# Airq_easyeda.net
KiCad netlist of a schematic drawn in EasyEDA
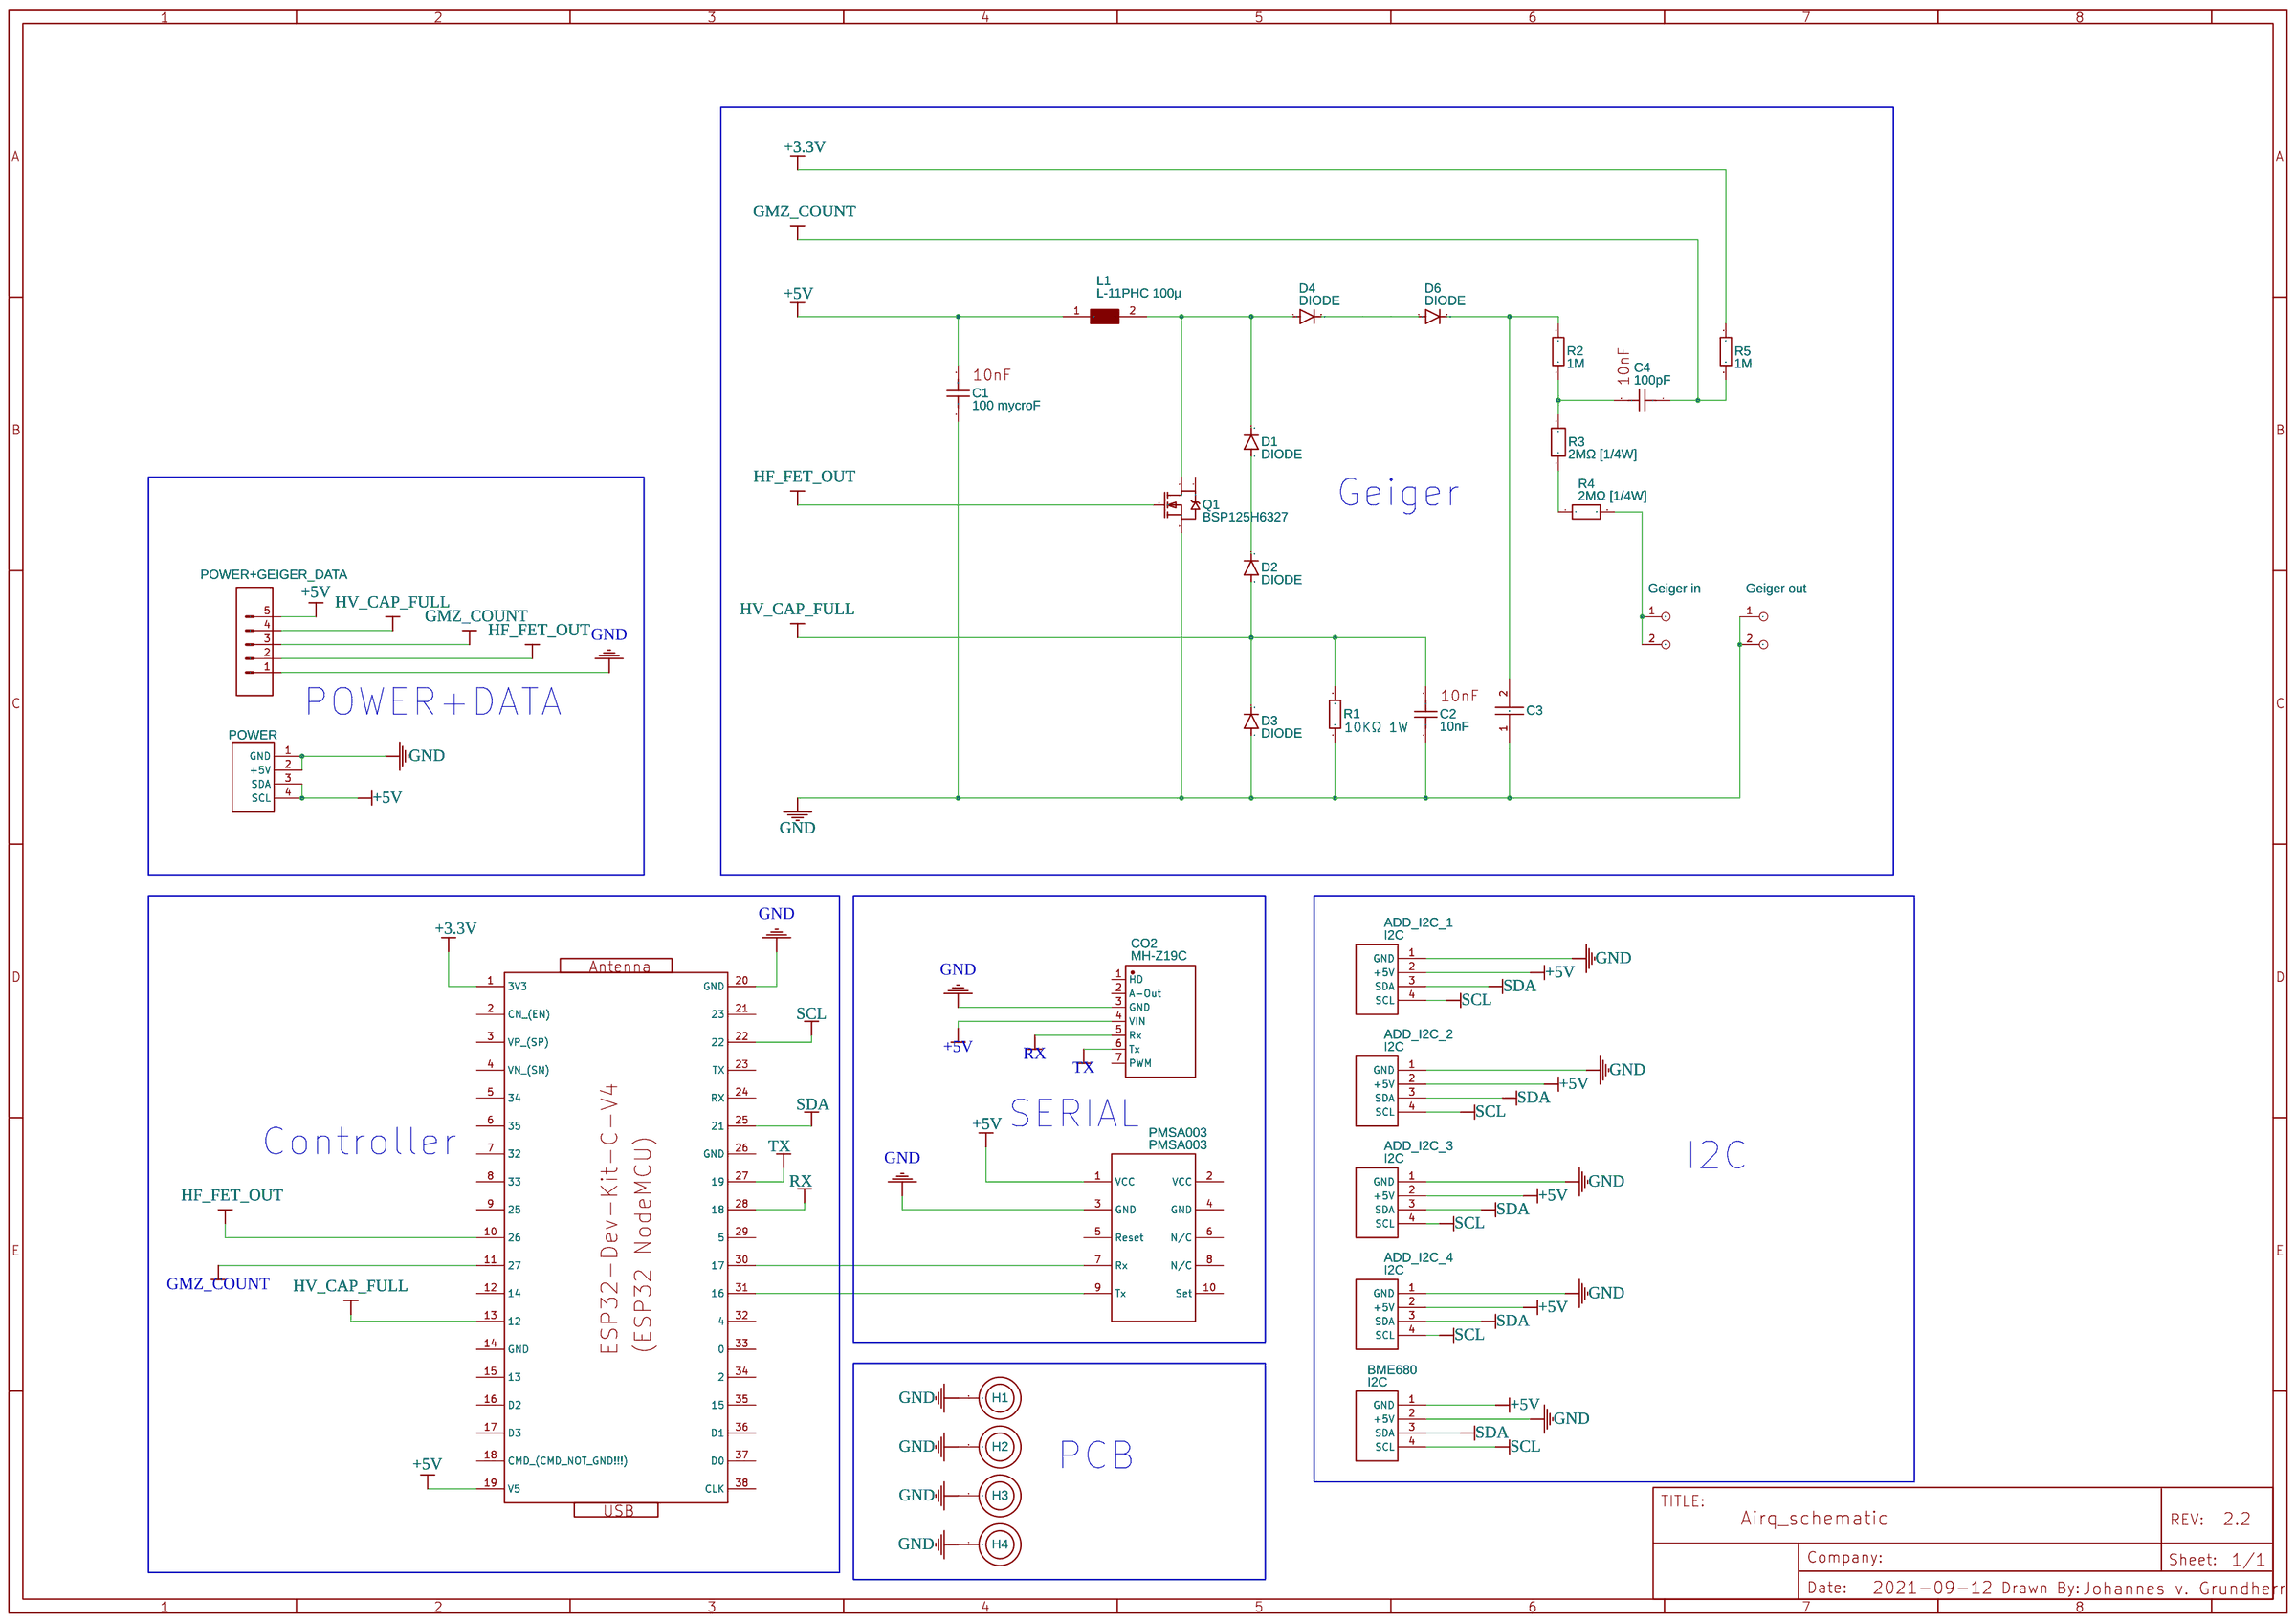
[diagram p0: schematic sheet]

(export (version "E")
  (design (tool "Eeschema 10.0.6"))
  (components
    (comp (ref "ADD_I2C_1") (value "I2C") (libsource (lib "") (part "I2C")))
    (comp (ref "ADD_I2C_2") (value "I2C") (libsource (lib "") (part "I2C")))
    (comp (ref "ADD_I2C_3") (value "I2C") (libsource (lib "") (part "I2C")))
    (comp (ref "ADD_I2C_4") (value "I2C") (libsource (lib "") (part "I2C")))
    (comp (ref "BME680") (value "I2C") (libsource (lib "") (part "I2C_1")))
    (comp (ref "C1") (value "100 mycroF") (libsource (lib "") (part "10nF")))
    (comp (ref "C2") (value "10nF") (libsource (lib "") (part "10nF")))
    (comp (ref "C3") (value "Wima, MKP4, 100nF, 630V") (libsource (lib "") (part "Wima, MKP4, 100nF, 630V")))
    (comp (ref "C4") (value "100pF") (libsource (lib "") (part "10nF_1")))
    (comp (ref "CO2")
      (value "MH-Z19C")
      (fields
        (field (name "BOM_Supplier Part") "https://github.com/WifWaf/MH-Z19/tree/master/examples/BasicUsage")
      )
      (libsource (lib "") (part "MH-Z19C"))
    )
    (comp (ref "D1") (value "DIODE") (libsource (lib "") (part "DIODE")))
    (comp (ref "D2") (value "DIODE") (libsource (lib "") (part "DIODE")))
    (comp (ref "D3") (value "DIODE") (libsource (lib "") (part "DIODE")))
    (comp (ref "D4") (value "DIODE") (libsource (lib "") (part "DIODE_1")))
    (comp (ref "D6") (value "DIODE") (libsource (lib "") (part "DIODE_1")))
    (comp (ref "H1") (value "HoleHole") (libsource (lib "") (part "HoleHole")))
    (comp (ref "H2") (value "HoleHole") (libsource (lib "") (part "HoleHole")))
    (comp (ref "H3") (value "HoleHole") (libsource (lib "") (part "HoleHole")))
    (comp (ref "H4") (value "HoleHole") (libsource (lib "") (part "HoleHole")))
    (comp (ref "JP1") (value "Geiger in") (libsource (lib "") (part "2 Pin Header")))
    (comp (ref "JP2") (value "Geiger out") (libsource (lib "") (part "2 Pin Header")))
    (comp (ref "L1") (value "L-11PHC 100µ") (libsource (lib "") (part "L-11PHC 100µ")))
    (comp (ref "PMSA003") (value "PMSA003") (libsource (lib "") (part "PMSA003")))
    (comp (ref "POWER") (value "Power") (libsource (lib "") (part "I2C_2")))
    (comp (ref "POWER+GEIGER_DATA") (value "POWER+GEIGER_DATA") (libsource (lib "") (part "Header 5pin")))
    (comp (ref "Q1")
      (value "BSP125H6327")
      (fields (field (name "BOM_Supplier Part") "C123756"))
      (libsource (lib "") (part "BSP125H6327"))
    )
    (comp (ref "R1")
      (value "10KΩ 1W")
      (fields
        (field (name "BOM_Manufacturer Part") "MFR0W4F1004A50")
        (field (name "BOM_Supplier Part") "C58596")
      )
      (libsource (lib "") (part "1M OHM_1"))
    )
    (comp (ref "R2")
      (value "1M")
      (fields
        (field (name "BOM_Manufacturer Part") "MFR0W4F1004A50")
        (field (name "BOM_Supplier Part") "C58596")
      )
      (libsource (lib "") (part "1M OHM_1"))
    )
    (comp (ref "R3")
      (value "2MΩ [1/4W]")
      (fields (field (name "BOM_Supplier Part") "C720290"))
      (libsource (lib "") (part "4.7MΩ [1/4W]"))
    )
    (comp (ref "R4")
      (value "2MΩ [1/4W]")
      (fields (field (name "BOM_Supplier Part") "C720290"))
      (libsource (lib "") (part "4.7MΩ [1/4W]_1"))
    )
    (comp (ref "R5")
      (value "1M")
      (fields
        (field (name "BOM_Manufacturer Part") "MFR0W4F1004A50")
        (field (name "BOM_Supplier Part") "C58596")
      )
      (libsource (lib "") (part "1M OHM"))
    )
    (comp (ref "U1")
      (value "AZDelivery_ESP32_NodeMCU")
      (libsource (lib "") (part "AZDelivery_ESP32_NodeMCU"))
    )
  )
  (nets
    (net (code "1") (name "+3.3V") (class "Default")
      (node (ref "R5") (pin "1") (pinfunction "1_1") (pintype "input"))
      (node (ref "U1") (pin "1") (pinfunction "3V3_1") (pintype "unspecified"))
    )
    (net (code "2") (name "+5V") (class "Default")
      (node (ref "ADD_I2C_1") (pin "2") (pinfunction "+5V_2") (pintype "unspecified"))
      (node (ref "ADD_I2C_2") (pin "2") (pinfunction "+5V_2") (pintype "unspecified"))
      (node (ref "ADD_I2C_3") (pin "2") (pinfunction "+5V_2") (pintype "unspecified"))
      (node (ref "ADD_I2C_4") (pin "2") (pinfunction "+5V_2") (pintype "unspecified"))
      (node (ref "BME680") (pin "1") (pinfunction "GND_1") (pintype "unspecified"))
      (node (ref "C1") (pin "2") (pinfunction "2_2") (pintype "unspecified"))
      (node (ref "CO2") (pin "4") (pinfunction "VIN_4") (pintype "passive"))
      (node (ref "L1") (pin "1") (pinfunction "1_1") (pintype "unspecified"))
      (node (ref "PMSA003") (pin "1") (pinfunction "VCC_1") (pintype "unspecified"))
      (node (ref "POWER") (pin "3") (pinfunction "SDA_3") (pintype "unspecified"))
      (node (ref "POWER") (pin "4") (pinfunction "SCL_4") (pintype "unspecified"))
      (node (ref "POWER+GEIGER_DATA") (pin "5") (pinfunction "1_5") (pintype "unspecified"))
      (node (ref "U1") (pin "19") (pinfunction "V5_19") (pintype "unspecified"))
    )
    (net (code "3") (name "GMZ_COUNT") (class "Default")
      (node (ref "C4") (pin "1") (pinfunction "1_1") (pintype "unspecified"))
      (node (ref "POWER+GEIGER_DATA") (pin "3") (pinfunction "1_3") (pintype "unspecified"))
      (node (ref "R5") (pin "2") (pinfunction "2_2") (pintype "input"))
      (node (ref "U1") (pin "11") (pinfunction "27_11") (pintype "unspecified"))
    )
    (net (code "4") (name "GND") (class "Default")
      (node (ref "ADD_I2C_1") (pin "1") (pinfunction "GND_1") (pintype "unspecified"))
      (node (ref "ADD_I2C_2") (pin "1") (pinfunction "GND_1") (pintype "unspecified"))
      (node (ref "ADD_I2C_3") (pin "1") (pinfunction "GND_1") (pintype "unspecified"))
      (node (ref "ADD_I2C_4") (pin "1") (pinfunction "GND_1") (pintype "unspecified"))
      (node (ref "BME680") (pin "2") (pinfunction "+5V_2") (pintype "unspecified"))
      (node (ref "C1") (pin "1") (pinfunction "1_1") (pintype "unspecified"))
      (node (ref "C2") (pin "1") (pinfunction "1_1") (pintype "unspecified"))
      (node (ref "C3") (pin "1") (pinfunction "1_1") (pintype "unspecified"))
      (node (ref "CO2") (pin "3") (pinfunction "GND_3") (pintype "passive"))
      (node (ref "D3") (pin "A") (pinfunction "A_A") (pintype "unspecified"))
      (node (ref "H1") (pin "1") (pinfunction "1_1") (pintype "bidirectional"))
      (node (ref "H2") (pin "1") (pinfunction "1_1") (pintype "bidirectional"))
      (node (ref "H3") (pin "1") (pinfunction "1_1") (pintype "bidirectional"))
      (node (ref "H4") (pin "1") (pinfunction "1_1") (pintype "bidirectional"))
      (node (ref "JP2") (pin "1") (pinfunction "1_1") (pintype "unspecified"))
      (node (ref "JP2") (pin "2") (pinfunction "2_2") (pintype "unspecified"))
      (node (ref "PMSA003") (pin "3") (pinfunction "GND_3") (pintype "unspecified"))
      (node (ref "POWER") (pin "1") (pinfunction "GND_1") (pintype "unspecified"))
      (node (ref "POWER") (pin "2") (pinfunction "+5V_2") (pintype "unspecified"))
      (node (ref "POWER+GEIGER_DATA") (pin "1") (pinfunction "1_1") (pintype "unspecified"))
      (node (ref "Q1") (pin "3") (pinfunction "S_3") (pintype "unspecified"))
      (node (ref "R1") (pin "1") (pinfunction "1_1") (pintype "input"))
      (node (ref "U1") (pin "20") (pinfunction "GND_20") (pintype "unspecified"))
    )
    (net (code "5") (name "HF_FET_OUT") (class "Default")
      (node (ref "POWER+GEIGER_DATA") (pin "2") (pinfunction "2_2") (pintype "unspecified"))
      (node (ref "Q1") (pin "1") (pinfunction "G_1") (pintype "unspecified"))
      (node (ref "U1") (pin "10") (pinfunction "26_10") (pintype "unspecified"))
    )
    (net (code "6") (name "HV_CAP_FULL") (class "Default")
      (node (ref "C2") (pin "2") (pinfunction "2_2") (pintype "unspecified"))
      (node (ref "D2") (pin "A") (pinfunction "A_A") (pintype "unspecified"))
      (node (ref "D3") (pin "C") (pinfunction "C_C") (pintype "unspecified"))
      (node (ref "POWER+GEIGER_DATA") (pin "4") (pinfunction "2_4") (pintype "unspecified"))
      (node (ref "R1") (pin "2") (pinfunction "2_2") (pintype "input"))
      (node (ref "U1") (pin "13") (pinfunction "12_13") (pintype "unspecified"))
    )
    (net (code "7") (name "Net-(C3-Pad2)") (class "Default")
      (node (ref "C3") (pin "2") (pinfunction "2_2") (pintype "unspecified"))
      (node (ref "D6") (pin "C") (pinfunction "C_C") (pintype "unspecified"))
      (node (ref "R2") (pin "2") (pinfunction "2_2") (pintype "input"))
    )
    (net (code "8") (name "Net-(C4-Pad2)") (class "Default")
      (node (ref "C4") (pin "2") (pinfunction "2_2") (pintype "unspecified"))
      (node (ref "R2") (pin "1") (pinfunction "1_1") (pintype "input"))
      (node (ref "R3") (pin "2") (pinfunction "2_2") (pintype "unspecified"))
    )
    (net (code "9") (name "Net-(D1-PadA)") (class "Default")
      (node (ref "D1") (pin "A") (pinfunction "A_A") (pintype "unspecified"))
      (node (ref "D2") (pin "C") (pinfunction "C_C") (pintype "unspecified"))
    )
    (net (code "10") (name "Net-(D1-PadC)") (class "Default")
      (node (ref "D1") (pin "C") (pinfunction "C_C") (pintype "unspecified"))
      (node (ref "D4") (pin "A") (pinfunction "A_A") (pintype "unspecified"))
      (node (ref "L1") (pin "2") (pinfunction "2_2") (pintype "unspecified"))
      (node (ref "Q1") (pin "2") (pinfunction "D_2") (pintype "unspecified"))
    )
    (net (code "11") (name "Net-(D4-PadC)") (class "Default")
      (node (ref "D4") (pin "C") (pinfunction "C_C") (pintype "unspecified"))
      (node (ref "D6") (pin "A") (pinfunction "A_A") (pintype "unspecified"))
    )
    (net (code "12") (name "Net-(JP1-Pad1)") (class "Default")
      (node (ref "JP1") (pin "1") (pinfunction "1_1") (pintype "unspecified"))
      (node (ref "JP1") (pin "2") (pinfunction "2_2") (pintype "unspecified"))
      (node (ref "R4") (pin "2") (pinfunction "2_2") (pintype "unspecified"))
    )
    (net (code "13") (name "Net-(PMSA003-Rx)") (class "Default")
      (node (ref "PMSA003") (pin "7") (pinfunction "Rx_7") (pintype "unspecified"))
      (node (ref "U1") (pin "30") (pinfunction "17_30") (pintype "unspecified"))
    )
    (net (code "14") (name "Net-(PMSA003-Tx)") (class "Default")
      (node (ref "PMSA003") (pin "9") (pinfunction "Tx_9") (pintype "unspecified"))
      (node (ref "U1") (pin "31") (pinfunction "16_31") (pintype "unspecified"))
    )
    (net (code "15") (name "Net-(R3-Pad1)") (class "Default")
      (node (ref "R3") (pin "1") (pinfunction "1_1") (pintype "unspecified"))
      (node (ref "R4") (pin "1") (pinfunction "1_1") (pintype "unspecified"))
    )
    (net (code "16") (name "RX") (class "Default")
      (node (ref "CO2") (pin "5") (pinfunction "Rx_5") (pintype "bidirectional"))
      (node (ref "U1") (pin "28") (pinfunction "18_28") (pintype "unspecified"))
    )
    (net (code "17") (name "SCL") (class "Default")
      (node (ref "ADD_I2C_1") (pin "4") (pinfunction "SCL_4") (pintype "unspecified"))
      (node (ref "ADD_I2C_2") (pin "4") (pinfunction "SCL_4") (pintype "unspecified"))
      (node (ref "ADD_I2C_3") (pin "4") (pinfunction "SCL_4") (pintype "unspecified"))
      (node (ref "ADD_I2C_4") (pin "4") (pinfunction "SCL_4") (pintype "unspecified"))
      (node (ref "BME680") (pin "4") (pinfunction "SCL_4") (pintype "unspecified"))
      (node (ref "U1") (pin "22") (pinfunction "22_22") (pintype "unspecified"))
    )
    (net (code "18") (name "SDA") (class "Default")
      (node (ref "ADD_I2C_1") (pin "3") (pinfunction "SDA_3") (pintype "unspecified"))
      (node (ref "ADD_I2C_2") (pin "3") (pinfunction "SDA_3") (pintype "unspecified"))
      (node (ref "ADD_I2C_3") (pin "3") (pinfunction "SDA_3") (pintype "unspecified"))
      (node (ref "ADD_I2C_4") (pin "3") (pinfunction "SDA_3") (pintype "unspecified"))
      (node (ref "BME680") (pin "3") (pinfunction "SDA_3") (pintype "unspecified"))
      (node (ref "U1") (pin "25") (pinfunction "21_25") (pintype "unspecified"))
    )
    (net (code "19") (name "TX") (class "Default")
      (node (ref "CO2") (pin "6") (pinfunction "Tx_6") (pintype "bidirectional"))
      (node (ref "U1") (pin "27") (pinfunction "19_27") (pintype "unspecified"))
    )
    (net (code "20") (name "unconnected-(CO2-A-Out-Pad2)") (class "Default")
      (node (ref "CO2") (pin "2") (pinfunction "A-Out_2") (pintype "output"))
    )
    (net (code "21") (name "unconnected-(CO2-HD-Pad1)") (class "Default")
      (node (ref "CO2") (pin "1") (pinfunction "HD_1") (pintype "unspecified"))
    )
    (net (code "22") (name "unconnected-(CO2-PWM-Pad7)") (class "Default")
      (node (ref "CO2") (pin "7") (pinfunction "PWM_7") (pintype "bidirectional"))
    )
    (net (code "23") (name "unconnected-(PMSA003-GND-Pad4)") (class "Default")
      (node (ref "PMSA003") (pin "4") (pinfunction "GND_4") (pintype "unspecified"))
    )
    (net (code "24") (name "unconnected-(PMSA003-N{slash}C-Pad6)") (class "Default")
      (node (ref "PMSA003") (pin "6") (pinfunction "N/C_6") (pintype "unspecified"))
    )
    (net (code "25") (name "unconnected-(PMSA003-N{slash}C-Pad8)") (class "Default")
      (node (ref "PMSA003") (pin "8") (pinfunction "N/C_8") (pintype "unspecified"))
    )
    (net (code "26") (name "unconnected-(PMSA003-Reset-Pad5)") (class "Default")
      (node (ref "PMSA003") (pin "5") (pinfunction "Reset_5") (pintype "unspecified"))
    )
    (net (code "27") (name "unconnected-(PMSA003-Set-Pad10)") (class "Default")
      (node (ref "PMSA003") (pin "10") (pinfunction "Set_10") (pintype "unspecified"))
    )
    (net (code "28") (name "unconnected-(PMSA003-VCC-Pad2)") (class "Default")
      (node (ref "PMSA003") (pin "2") (pinfunction "VCC_2") (pintype "unspecified"))
    )
    (net (code "29") (name "unconnected-(Q1-D-Pad4)") (class "Default")
      (node (ref "Q1") (pin "4") (pinfunction "D_4") (pintype "unspecified"))
    )
    (net (code "30") (name "unconnected-(U1-0-Pad33)") (class "Default")
      (node (ref "U1") (pin "33") (pinfunction "0_33") (pintype "unspecified"))
    )
    (net (code "31") (name "unconnected-(U1-2-Pad34)") (class "Default")
      (node (ref "U1") (pin "34") (pinfunction "2_34") (pintype "unspecified"))
    )
    (net (code "32") (name "unconnected-(U1-4-Pad32)") (class "Default")
      (node (ref "U1") (pin "32") (pinfunction "4_32") (pintype "unspecified"))
    )
    (net (code "33") (name "unconnected-(U1-5-Pad29)") (class "Default")
      (node (ref "U1") (pin "29") (pinfunction "5_29") (pintype "unspecified"))
    )
    (net (code "34") (name "unconnected-(U1-13-Pad15)") (class "Default")
      (node (ref "U1") (pin "15") (pinfunction "13_15") (pintype "unspecified"))
    )
    (net (code "35") (name "unconnected-(U1-14-Pad12)") (class "Default")
      (node (ref "U1") (pin "12") (pinfunction "14_12") (pintype "unspecified"))
    )
    (net (code "36") (name "unconnected-(U1-15-Pad35)") (class "Default")
      (node (ref "U1") (pin "35") (pinfunction "15_35") (pintype "unspecified"))
    )
    (net (code "37") (name "unconnected-(U1-23-Pad21)") (class "Default")
      (node (ref "U1") (pin "21") (pinfunction "23_21") (pintype "unspecified"))
    )
    (net (code "38") (name "unconnected-(U1-25-Pad9)") (class "Default")
      (node (ref "U1") (pin "9") (pinfunction "25_9") (pintype "unspecified"))
    )
    (net (code "39") (name "unconnected-(U1-32-Pad7)") (class "Default")
      (node (ref "U1") (pin "7") (pinfunction "32_7") (pintype "unspecified"))
    )
    (net (code "40") (name "unconnected-(U1-33-Pad8)") (class "Default")
      (node (ref "U1") (pin "8") (pinfunction "33_8") (pintype "unspecified"))
    )
    (net (code "41") (name "unconnected-(U1-34-Pad5)") (class "Default")
      (node (ref "U1") (pin "5") (pinfunction "34_5") (pintype "unspecified"))
    )
    (net (code "42") (name "unconnected-(U1-35-Pad6)") (class "Default")
      (node (ref "U1") (pin "6") (pinfunction "35_6") (pintype "unspecified"))
    )
    (net (code "43") (name "unconnected-(U1-CLK-Pad38)") (class "Default")
      (node (ref "U1") (pin "38") (pinfunction "CLK_38") (pintype "unspecified"))
    )
    (net (code "44") (name "unconnected-(U1-CMD_(CMD_NOT_GND!!!)-Pad18)") (class "Default")
      (node (ref "U1") (pin "18") (pinfunction "CMD_(CMD_NOT_GND!!!)_18") (pintype "unspecified"))
    )
    (net (code "45") (name "unconnected-(U1-CN_(EN)-Pad2)") (class "Default")
      (node (ref "U1") (pin "2") (pinfunction "CN_(EN)_2") (pintype "unspecified"))
    )
    (net (code "46") (name "unconnected-(U1-D0-Pad37)") (class "Default")
      (node (ref "U1") (pin "37") (pinfunction "D0_37") (pintype "unspecified"))
    )
    (net (code "47") (name "unconnected-(U1-D1-Pad36)") (class "Default")
      (node (ref "U1") (pin "36") (pinfunction "D1_36") (pintype "unspecified"))
    )
    (net (code "48") (name "unconnected-(U1-D2-Pad16)") (class "Default")
      (node (ref "U1") (pin "16") (pinfunction "D2_16") (pintype "unspecified"))
    )
    (net (code "49") (name "unconnected-(U1-D3-Pad17)") (class "Default")
      (node (ref "U1") (pin "17") (pinfunction "D3_17") (pintype "unspecified"))
    )
    (net (code "50") (name "unconnected-(U1-GND-Pad14)") (class "Default")
      (node (ref "U1") (pin "14") (pinfunction "GND_14") (pintype "unspecified"))
    )
    (net (code "51") (name "unconnected-(U1-GND-Pad26)") (class "Default")
      (node (ref "U1") (pin "26") (pinfunction "GND_26") (pintype "unspecified"))
    )
    (net (code "52") (name "unconnected-(U1-RX-Pad24)") (class "Default")
      (node (ref "U1") (pin "24") (pinfunction "RX_24") (pintype "unspecified"))
    )
    (net (code "53") (name "unconnected-(U1-TX-Pad23)") (class "Default")
      (node (ref "U1") (pin "23") (pinfunction "TX_23") (pintype "unspecified"))
    )
    (net (code "54") (name "unconnected-(U1-VN_(SN)-Pad4)") (class "Default")
      (node (ref "U1") (pin "4") (pinfunction "VN_(SN)_4") (pintype "unspecified"))
    )
    (net (code "55") (name "unconnected-(U1-VP_(SP)-Pad3)") (class "Default")
      (node (ref "U1") (pin "3") (pinfunction "VP_(SP)_3") (pintype "unspecified"))
    )
  )
)
